# ZERO.net
KiCad netlist of a schematic drawn in Altium Designer
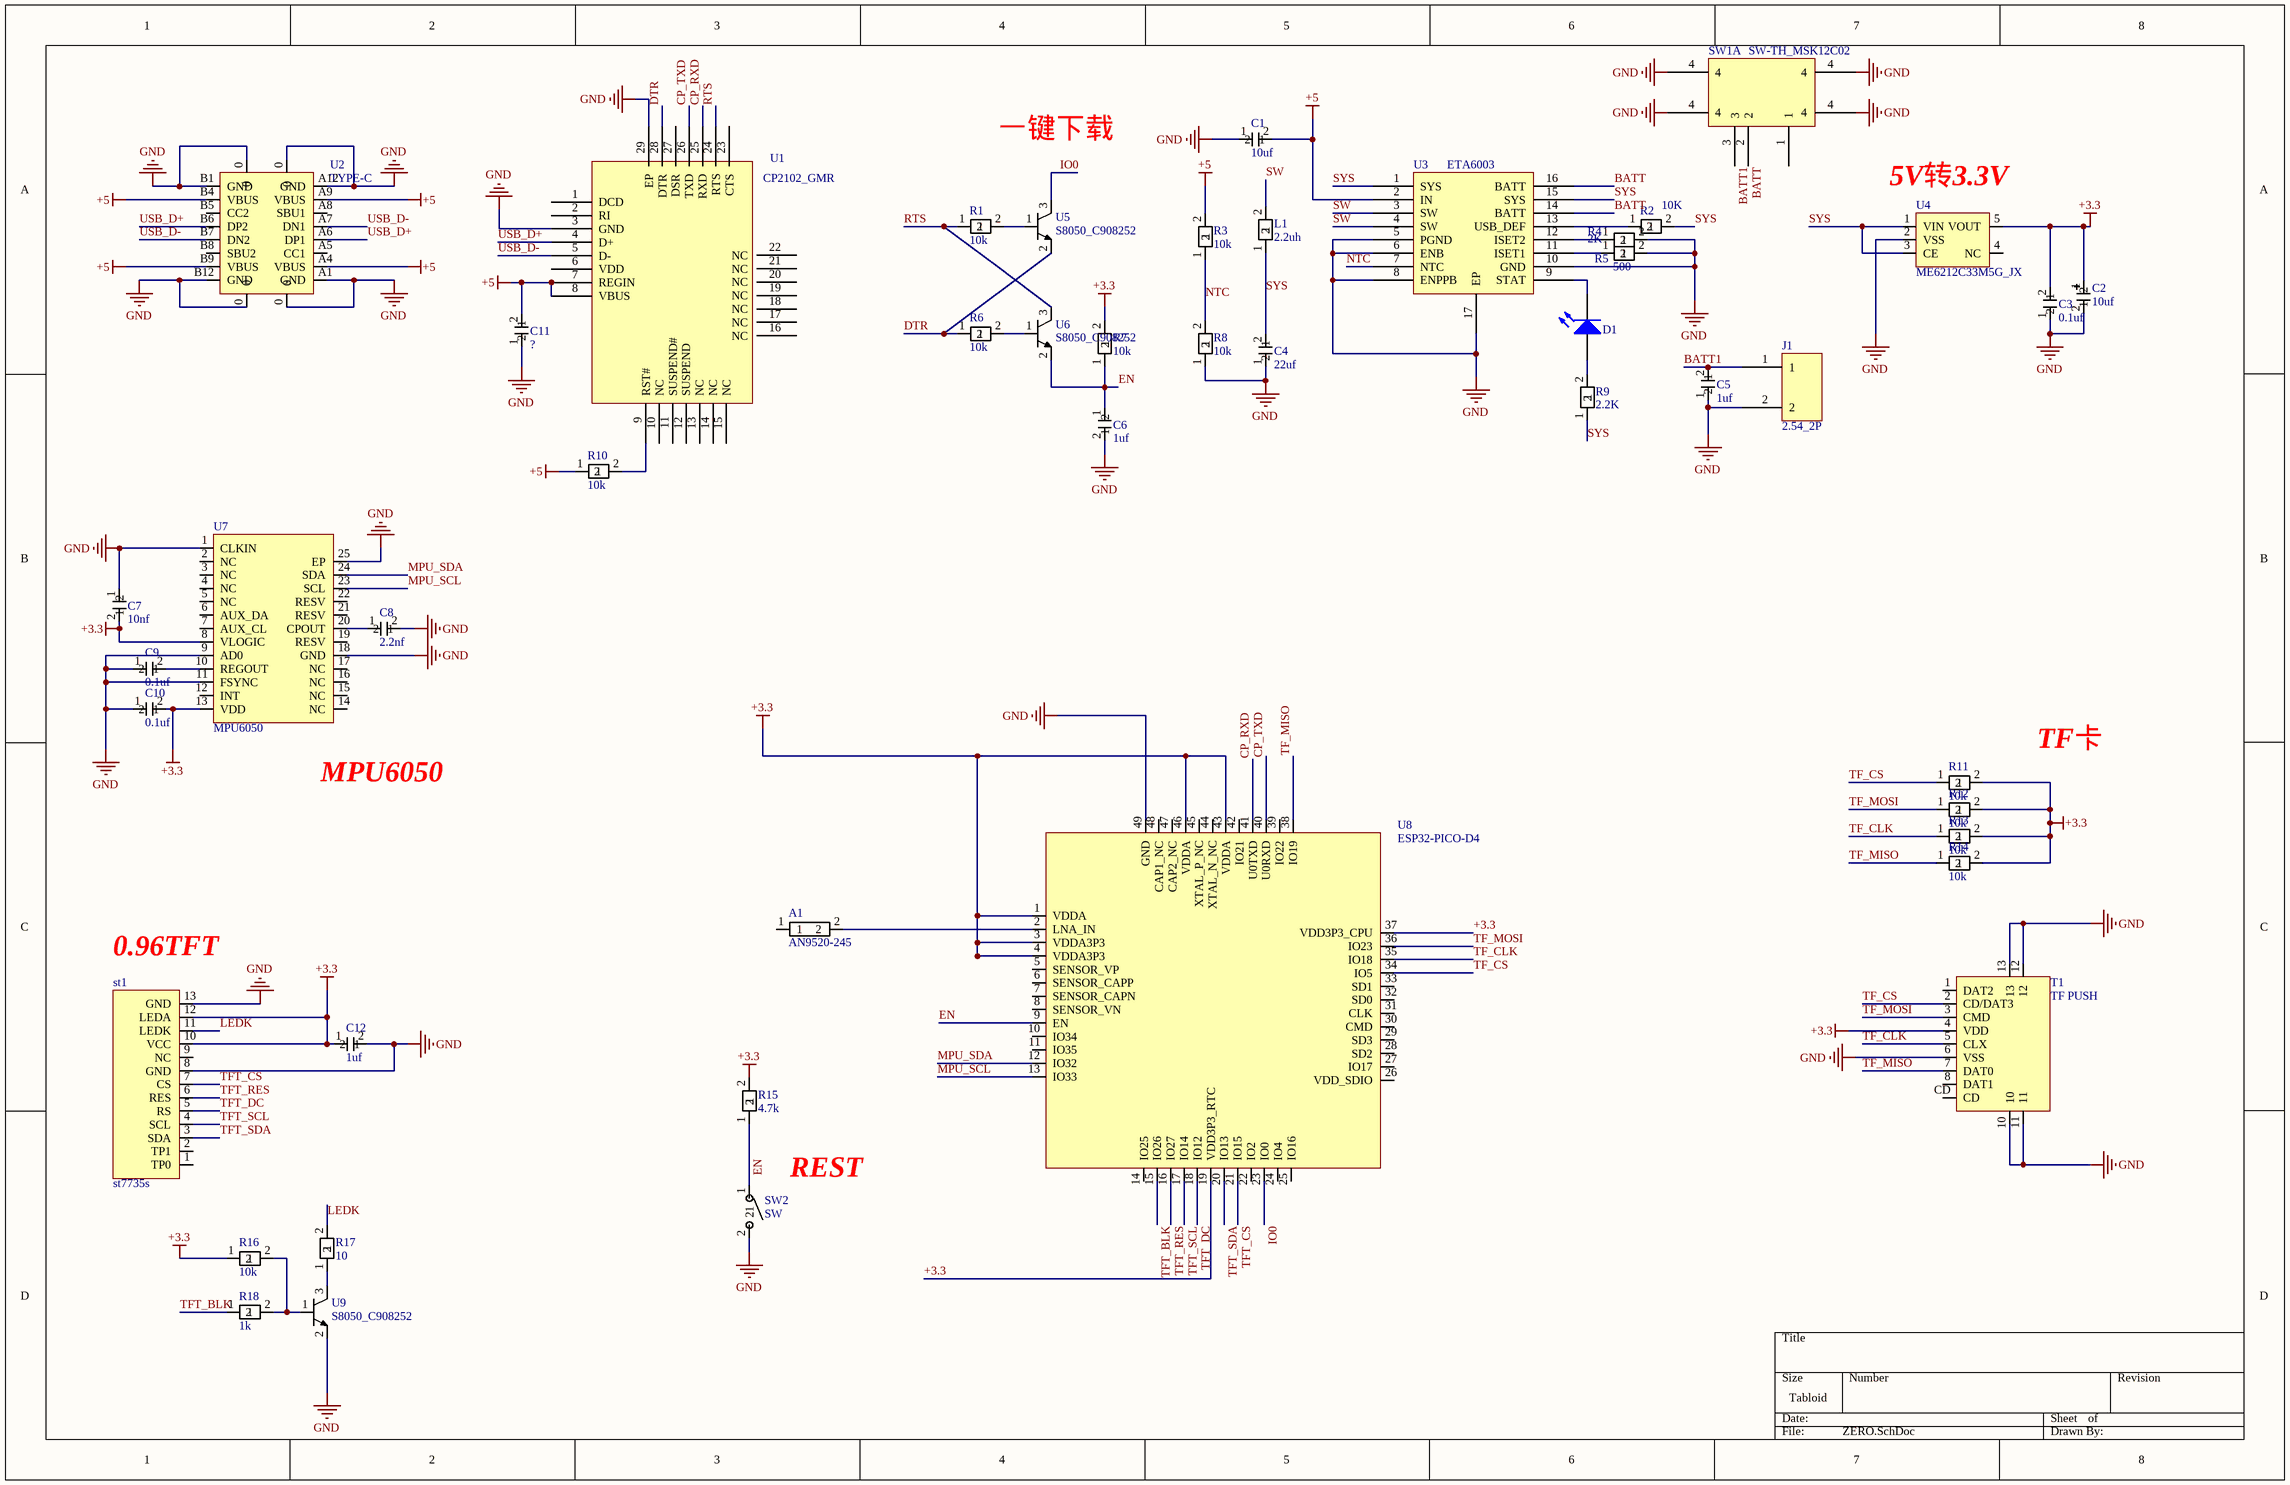
[diagram p0: ZERO.SchDoc]

(export (version "E")
  (design (tool "Eeschema 10.0.6"))
  (components
    (comp (ref "A1") (value "AN9520-245") (footprint "AN9520-245") (libsource (lib "My") (part "AN9520-245")))
    (comp (ref "C1") (value "10uf") (footprint "C0805") (libsource (lib "My") (part "C0805")))
    (comp (ref "C2") (value "10uf") (footprint "C+") (libsource (lib "My") (part "C+")))
    (comp (ref "C3") (value "0.1uf") (footprint "C0805") (libsource (lib "Schlib1") (part "C0805")))
    (comp (ref "C4") (value "22uf") (footprint "C0805") (libsource (lib "My") (part "C0805")))
    (comp (ref "C5") (value "1uf") (footprint "C0805") (libsource (lib "My") (part "C0805")))
    (comp (ref "C6") (value "1uf") (footprint "C0805") (libsource (lib "Schlib1") (part "C0805")))
    (comp (ref "C7") (value "10nf") (footprint "C0805") (libsource (lib "Schlib1") (part "C0805")))
    (comp (ref "C8") (value "2.2nf") (footprint "C0805") (libsource (lib "Schlib1") (part "C0805")))
    (comp (ref "C9") (value "0.1uf") (footprint "C0805") (libsource (lib "Schlib1") (part "C0805")))
    (comp (ref "C10") (value "0.1uf") (footprint "C0805") (libsource (lib "Schlib1") (part "C0805")))
    (comp (ref "C11") (value "?") (footprint "C0805") (libsource (lib "My") (part "C0805")))
    (comp (ref "C12") (value "1uf") (footprint "C0805") (libsource (lib "Schlib1") (part "C0805")))
    (comp (ref "D1")
      (value "LED 蓝 0805")
      (footprint "LED 蓝  0805")
      (libsource (lib "改好的库") (part "LED 蓝 0805"))
    )
    (comp (ref "J1") (value "2.54_2P") (footprint "2.54-2P") (libsource (lib "My") (part "2.54_2P")))
    (comp (ref "L1") (value "2.2uh") (footprint "R0805") (libsource (lib "My") (part "R0805")))
    (comp (ref "R1") (value "10k") (footprint "R0805") (libsource (lib "Schlib1") (part "R0805")))
    (comp (ref "R2") (value "10K") (footprint "R0805") (libsource (lib "My") (part "R0805")))
    (comp (ref "R3") (value "10k") (footprint "R0805") (libsource (lib "My") (part "R0805")))
    (comp (ref "R4") (value "2K") (footprint "R0805") (libsource (lib "My") (part "R0805")))
    (comp (ref "R5") (value "500") (footprint "R0805") (libsource (lib "My") (part "R0805")))
    (comp (ref "R6") (value "10k") (footprint "R0805") (libsource (lib "Schlib1") (part "R0805")))
    (comp (ref "R7") (value "10k") (footprint "R0805") (libsource (lib "Schlib1") (part "R0805")))
    (comp (ref "R8") (value "10k") (footprint "R0805") (libsource (lib "My") (part "R0805")))
    (comp (ref "R9") (value "2.2K") (footprint "R0805") (libsource (lib "My") (part "R0805")))
    (comp (ref "R10") (value "10k") (footprint "R0805") (libsource (lib "My") (part "R0805")))
    (comp (ref "R11") (value "10k") (footprint "R0805") (libsource (lib "Schlib1") (part "R0805")))
    (comp (ref "R12") (value "10k") (footprint "R0805") (libsource (lib "Schlib1") (part "R0805")))
    (comp (ref "R13") (value "10k") (footprint "R0805") (libsource (lib "Schlib1") (part "R0805")))
    (comp (ref "R14") (value "10k") (footprint "R0805") (libsource (lib "Schlib1") (part "R0805")))
    (comp (ref "R15") (value "4.7k") (footprint "R0805") (libsource (lib "Schlib1") (part "R0805")))
    (comp (ref "R16") (value "10k") (footprint "R0805") (libsource (lib "Schlib1") (part "R0805")))
    (comp (ref "R17") (value "10") (footprint "R0805") (libsource (lib "Schlib1") (part "R0805")))
    (comp (ref "R18") (value "1k") (footprint "R0805") (libsource (lib "Schlib1") (part "R0805")))
    (comp (ref "st1") (value "st7735s") (footprint "st7735s") (libsource (lib "Schlib1") (part "st7735s")))
    (comp (ref "SW1")
      (value "SW-TH_MSK12C02")
      (footprint "SW-TH_MSK12C02")
      (libsource (lib "My") (part "SW-TH_MSK12C02"))
    )
    (comp (ref "SW2") (value "SW") (footprint "SW") (libsource (lib "My") (part "SW")))
    (comp (ref "T1") (value "TF PUSH") (footprint "TF-SMD_TF-PUSH") (libsource (lib "My") (part "TF PUSH")))
    (comp (ref "U1") (value "CP2102_GMR") (footprint "CP2102_GMR") (libsource (lib "My") (part "CP2102_GMR")))
    (comp (ref "U2")
      (value "TYPE-C")
      (footprint "USB-C")
      (description "TYPE-C-31-M-12")
      (libsource (lib "My") (part "TYPE-C"))
    )
    (comp (ref "U3") (value "ETA6003") (footprint "ETA6003") (libsource (lib "My") (part "ETA6003")))
    (comp (ref "U4")
      (value "ME6212C33M5G_JX")
      (footprint "ME6212C33M5G_JX")
      (libsource (lib "My") (part "ME6212C33M5G_JX"))
    )
    (comp (ref "U5") (value "S8050_C908252") (footprint "s8050") (libsource (lib "My") (part "s8050")))
    (comp (ref "U6") (value "S8050_C908252") (footprint "s8050") (libsource (lib "My") (part "s8050")))
    (comp (ref "U7") (value "MPU6050") (footprint "MPU6050") (libsource (lib "My") (part "MPU6050")))
    (comp (ref "U8")
      (value "ESP32-PICO-D4")
      (footprint "ESP32-PICO-D4")
      (libsource (lib "My") (part "ESP32-PICO-D4"))
    )
    (comp (ref "U9") (value "S8050_C908252") (footprint "s8050") (libsource (lib "My") (part "s8050")))
  )
  (nets
    (net (code "1") (name "+3.3") (class "Default")
      (node (ref "C10") (pin "2") (pinfunction "2_2") (pintype "passive"))
      (node (ref "C12") (pin "1") (pinfunction "1_1") (pintype "passive"))
      (node (ref "C2") (pin "1") (pinfunction "1_1") (pintype "passive"))
      (node (ref "C3") (pin "2") (pinfunction "2_2") (pintype "passive"))
      (node (ref "C7") (pin "2") (pinfunction "2_2") (pintype "passive"))
      (node (ref "R11") (pin "2") (pinfunction "2_2") (pintype "passive"))
      (node (ref "R12") (pin "2") (pinfunction "2_2") (pintype "passive"))
      (node (ref "R13") (pin "2") (pinfunction "2_2") (pintype "passive"))
      (node (ref "R14") (pin "2") (pinfunction "2_2") (pintype "passive"))
      (node (ref "R15") (pin "2") (pinfunction "2_2") (pintype "passive"))
      (node (ref "R16") (pin "1") (pinfunction "1_1") (pintype "passive"))
      (node (ref "R7") (pin "2") (pinfunction "2_2") (pintype "passive"))
      (node (ref "T1") (pin "4") (pinfunction "VDD_4") (pintype "passive"))
      (node (ref "U4") (pin "5") (pinfunction "VOUT_5") (pintype "passive"))
      (node (ref "U7") (pin "13") (pinfunction "VDD_13") (pintype "passive"))
      (node (ref "U7") (pin "8") (pinfunction "VLOGIC_8") (pintype "passive"))
      (node (ref "U8") (pin "1") (pinfunction "VDDA_1") (pintype "passive"))
      (node (ref "U8") (pin "19") (pinfunction "VDD3P3_RTC_19") (pintype "passive"))
      (node (ref "U8") (pin "3") (pinfunction "VDDA3P3_3") (pintype "passive"))
      (node (ref "U8") (pin "37") (pinfunction "VDD3P3_CPU_37") (pintype "passive"))
      (node (ref "U8") (pin "4") (pinfunction "VDDA3P3_4") (pintype "passive"))
      (node (ref "U8") (pin "43") (pinfunction "VDDA_43") (pintype "passive"))
      (node (ref "U8") (pin "46") (pinfunction "VDDA_46") (pintype "passive"))
      (node (ref "st1") (pin "10") (pinfunction "VCC_10") (pintype "passive"))
      (node (ref "st1") (pin "12") (pinfunction "LEDA_12") (pintype "passive"))
    )
    (net (code "2") (name "+5") (class "Default")
      (node (ref "C1") (pin "2") (pinfunction "2_2") (pintype "passive"))
      (node (ref "C11") (pin "2") (pinfunction "2_2") (pintype "passive"))
      (node (ref "R10") (pin "1") (pinfunction "1_1") (pintype "passive"))
      (node (ref "R3") (pin "2") (pinfunction "2_2") (pintype "passive"))
      (node (ref "U1") (pin "7") (pinfunction "REGIN_7") (pintype "passive"))
      (node (ref "U1") (pin "8") (pinfunction "VBUS_8") (pintype "passive"))
      (node (ref "U2") (pin "A4") (pinfunction "VBUS_A4") (pintype "passive"))
      (node (ref "U2") (pin "A9") (pinfunction "VBUS_A9") (pintype "passive"))
      (node (ref "U2") (pin "B4") (pinfunction "VBUS_B4") (pintype "passive"))
      (node (ref "U2") (pin "B9") (pinfunction "VBUS_B9") (pintype "passive"))
      (node (ref "U3") (pin "2") (pinfunction "IN_2") (pintype "passive"))
    )
    (net (code "4") (name "/BATT") (class "Default")
      (node (ref "SW1") (pin "2") (pinfunction "2_2") (pintype "passive"))
      (node (ref "U3") (pin "14") (pinfunction "BATT_14") (pintype "passive"))
      (node (ref "U3") (pin "16") (pinfunction "BATT_16") (pintype "passive"))
    )
    (net (code "5") (name "/BATT1") (class "Default")
      (node (ref "C5") (pin "2") (pinfunction "2_2") (pintype "passive"))
      (node (ref "J1") (pin "1") (pinfunction "1_1") (pintype "passive"))
      (node (ref "SW1") (pin "3") (pinfunction "3_3") (pintype "passive"))
    )
    (net (code "6") (name "/CP_RXD") (class "Default")
      (node (ref "U1") (pin "25") (pinfunction "RXD_25") (pintype "passive"))
      (node (ref "U8") (pin "41") (pinfunction "U0TXD_41") (pintype "passive"))
    )
    (net (code "7") (name "/CP_TXD") (class "Default")
      (node (ref "U1") (pin "26") (pinfunction "TXD_26") (pintype "passive"))
      (node (ref "U8") (pin "40") (pinfunction "U0RXD_40") (pintype "passive"))
    )
    (net (code "8") (name "/DTR") (class "Default")
      (node (ref "R6") (pin "1") (pinfunction "1_1") (pintype "passive"))
      (node (ref "U1") (pin "28") (pinfunction "DTR_28") (pintype "passive"))
      (node (ref "U5") (pin "2") (pinfunction "E_2") (pintype "passive"))
    )
    (net (code "9") (name "/EN") (class "Default")
      (node (ref "C6") (pin "1") (pinfunction "1_1") (pintype "passive"))
      (node (ref "R15") (pin "1") (pinfunction "1_1") (pintype "passive"))
      (node (ref "R7") (pin "1") (pinfunction "1_1") (pintype "passive"))
      (node (ref "SW2") (pin "1") (pinfunction "1_1") (pintype "passive"))
      (node (ref "U6") (pin "2") (pinfunction "E_2") (pintype "passive"))
      (node (ref "U8") (pin "9") (pinfunction "EN_9") (pintype "passive"))
    )
    (net (code "10") (name "/IO0") (class "Default")
      (node (ref "U5") (pin "3") (pinfunction "C_3") (pintype "passive"))
      (node (ref "U8") (pin "23") (pinfunction "IO0_23") (pintype "passive"))
    )
    (net (code "11") (name "/LEDK") (class "Default")
      (node (ref "R17") (pin "2") (pinfunction "2_2") (pintype "passive"))
      (node (ref "st1") (pin "11") (pinfunction "LEDK_11") (pintype "passive"))
    )
    (net (code "12") (name "/MPU_SCL") (class "Default")
      (node (ref "U7") (pin "23") (pinfunction "SCL_23") (pintype "passive"))
      (node (ref "U8") (pin "13") (pinfunction "IO33_13") (pintype "passive"))
    )
    (net (code "13") (name "/MPU_SDA") (class "Default")
      (node (ref "U7") (pin "24") (pinfunction "SDA_24") (pintype "passive"))
      (node (ref "U8") (pin "12") (pinfunction "IO32_12") (pintype "passive"))
    )
    (net (code "14") (name "/NTC") (class "Default")
      (node (ref "R3") (pin "1") (pinfunction "1_1") (pintype "passive"))
      (node (ref "R8") (pin "2") (pinfunction "2_2") (pintype "passive"))
      (node (ref "U3") (pin "7") (pinfunction "NTC_7") (pintype "passive"))
    )
    (net (code "15") (name "/RTS") (class "Default")
      (node (ref "R1") (pin "1") (pinfunction "1_1") (pintype "passive"))
      (node (ref "U1") (pin "24") (pinfunction "RTS_24") (pintype "passive"))
      (node (ref "U6") (pin "3") (pinfunction "C_3") (pintype "passive"))
    )
    (net (code "16") (name "/SW") (class "Default")
      (node (ref "L1") (pin "2") (pinfunction "2_2") (pintype "passive"))
      (node (ref "U3") (pin "3") (pinfunction "SW_3") (pintype "passive"))
      (node (ref "U3") (pin "4") (pinfunction "SW_4") (pintype "passive"))
    )
    (net (code "17") (name "/SYS") (class "Default")
      (node (ref "C4") (pin "2") (pinfunction "2_2") (pintype "passive"))
      (node (ref "L1") (pin "1") (pinfunction "1_1") (pintype "passive"))
      (node (ref "R2") (pin "2") (pinfunction "2_2") (pintype "passive"))
      (node (ref "R9") (pin "1") (pinfunction "1_1") (pintype "passive"))
      (node (ref "U3") (pin "1") (pinfunction "SYS_1") (pintype "passive"))
      (node (ref "U3") (pin "15") (pinfunction "SYS_15") (pintype "passive"))
      (node (ref "U4") (pin "1") (pinfunction "VIN_1") (pintype "passive"))
      (node (ref "U4") (pin "3") (pinfunction "CE_3") (pintype "passive"))
    )
    (net (code "18") (name "/TFT_BLK") (class "Default")
      (node (ref "R18") (pin "1") (pinfunction "1_1") (pintype "passive"))
      (node (ref "U8") (pin "15") (pinfunction "IO26_15") (pintype "passive"))
    )
    (net (code "19") (name "/TFT_CS") (class "Default")
      (node (ref "U8") (pin "21") (pinfunction "IO15_21") (pintype "passive"))
      (node (ref "st1") (pin "7") (pinfunction "CS_7") (pintype "passive"))
    )
    (net (code "20") (name "/TFT_DC") (class "Default")
      (node (ref "U8") (pin "18") (pinfunction "IO12_18") (pintype "passive"))
      (node (ref "st1") (pin "5") (pinfunction "RS_5") (pintype "passive"))
    )
    (net (code "21") (name "/TFT_RES") (class "Default")
      (node (ref "U8") (pin "16") (pinfunction "IO27_16") (pintype "passive"))
      (node (ref "st1") (pin "6") (pinfunction "RES_6") (pintype "passive"))
    )
    (net (code "22") (name "/TFT_SCL") (class "Default")
      (node (ref "U8") (pin "17") (pinfunction "IO14_17") (pintype "passive"))
      (node (ref "st1") (pin "4") (pinfunction "SCL_4") (pintype "passive"))
    )
    (net (code "23") (name "/TFT_SDA") (class "Default")
      (node (ref "U8") (pin "20") (pinfunction "IO13_20") (pintype "passive"))
      (node (ref "st1") (pin "3") (pinfunction "SDA_3") (pintype "passive"))
    )
    (net (code "24") (name "/TF_CLK") (class "Default")
      (node (ref "R13") (pin "1") (pinfunction "1_1") (pintype "passive"))
      (node (ref "T1") (pin "5") (pinfunction "CLX_5") (pintype "passive"))
      (node (ref "U8") (pin "35") (pinfunction "IO18_35") (pintype "passive"))
    )
    (net (code "25") (name "/TF_CS") (class "Default")
      (node (ref "R11") (pin "1") (pinfunction "1_1") (pintype "passive"))
      (node (ref "T1") (pin "2") (pinfunction "CD/DAT3_2") (pintype "passive"))
      (node (ref "U8") (pin "34") (pinfunction "IO5_34") (pintype "passive"))
    )
    (net (code "26") (name "/TF_MISO") (class "Default")
      (node (ref "R14") (pin "1") (pinfunction "1_1") (pintype "passive"))
      (node (ref "T1") (pin "7") (pinfunction "DAT0_7") (pintype "passive"))
      (node (ref "U8") (pin "38") (pinfunction "IO19_38") (pintype "passive"))
    )
    (net (code "27") (name "/TF_MOSI") (class "Default")
      (node (ref "R12") (pin "1") (pinfunction "1_1") (pintype "passive"))
      (node (ref "T1") (pin "3") (pinfunction "CMD_3") (pintype "passive"))
      (node (ref "U8") (pin "36") (pinfunction "IO23_36") (pintype "passive"))
    )
    (net (code "28") (name "/USB_D+") (class "Default")
      (node (ref "U1") (pin "4") (pinfunction "D+_4") (pintype "passive"))
      (node (ref "U2") (pin "A6") (pinfunction "DP1_A6") (pintype "passive"))
      (node (ref "U2") (pin "B6") (pinfunction "DP2_B6") (pintype "passive"))
    )
    (net (code "29") (name "/USB_D-") (class "Default")
      (node (ref "U1") (pin "5") (pinfunction "D-_5") (pintype "passive"))
      (node (ref "U2") (pin "A7") (pinfunction "DN1_A7") (pintype "passive"))
      (node (ref "U2") (pin "B7") (pinfunction "DN2_B7") (pintype "passive"))
    )
    (net (code "30") (name "GND") (class "Default")
      (node (ref "C1") (pin "1") (pinfunction "1_1") (pintype "passive"))
      (node (ref "C10") (pin "1") (pinfunction "1_1") (pintype "passive"))
      (node (ref "C11") (pin "1") (pinfunction "1_1") (pintype "passive"))
      (node (ref "C12") (pin "2") (pinfunction "2_2") (pintype "passive"))
      (node (ref "C2") (pin "2") (pinfunction "2_2") (pintype "passive"))
      (node (ref "C3") (pin "1") (pinfunction "1_1") (pintype "passive"))
      (node (ref "C4") (pin "1") (pinfunction "1_1") (pintype "passive"))
      (node (ref "C5") (pin "1") (pinfunction "1_1") (pintype "passive"))
      (node (ref "C6") (pin "2") (pinfunction "2_2") (pintype "passive"))
      (node (ref "C7") (pin "1") (pinfunction "1_1") (pintype "passive"))
      (node (ref "C8") (pin "2") (pinfunction "2_2") (pintype "passive"))
      (node (ref "C9") (pin "1") (pinfunction "1_1") (pintype "passive"))
      (node (ref "J1") (pin "2") (pinfunction "2_2") (pintype "passive"))
      (node (ref "R4") (pin "2") (pinfunction "2_2") (pintype "passive"))
      (node (ref "R5") (pin "2") (pinfunction "2_2") (pintype "passive"))
      (node (ref "R8") (pin "1") (pinfunction "1_1") (pintype "passive"))
      (node (ref "SW1") (pin "4") (pinfunction "4_4") (pintype "passive"))
      (node (ref "SW2") (pin "2") (pinfunction "2_2") (pintype "passive"))
      (node (ref "T1") (pin "10") (pinfunction "10_10") (pintype "passive"))
      (node (ref "T1") (pin "11") (pinfunction "11_11") (pintype "passive"))
      (node (ref "T1") (pin "12") (pinfunction "12_12") (pintype "passive"))
      (node (ref "T1") (pin "13") (pinfunction "13_13") (pintype "passive"))
      (node (ref "T1") (pin "6") (pinfunction "VSS_6") (pintype "passive"))
      (node (ref "U1") (pin "29") (pinfunction "EP_29") (pintype "passive"))
      (node (ref "U1") (pin "3") (pinfunction "GND_3") (pintype "passive"))
      (node (ref "U2") (pin "0") (pinfunction "0_0") (pintype "passive"))
      (node (ref "U2") (pin "A1") (pinfunction "GND_A1") (pintype "passive"))
      (node (ref "U2") (pin "A12") (pinfunction "GND_A12") (pintype "passive"))
      (node (ref "U2") (pin "B1") (pinfunction "GND_B1") (pintype "passive"))
      (node (ref "U2") (pin "B12") (pinfunction "GND_B12") (pintype "passive"))
      (node (ref "U3") (pin "10") (pinfunction "GND_10") (pintype "passive"))
      (node (ref "U3") (pin "17") (pinfunction "EP_17") (pintype "passive"))
      (node (ref "U3") (pin "5") (pinfunction "PGND_5") (pintype "passive"))
      (node (ref "U3") (pin "6") (pinfunction "ENB_6") (pintype "passive"))
      (node (ref "U3") (pin "8") (pinfunction "ENPPB_8") (pintype "passive"))
      (node (ref "U4") (pin "2") (pinfunction "VSS_2") (pintype "passive"))
      (node (ref "U7") (pin "1") (pinfunction "CLKIN_1") (pintype "passive"))
      (node (ref "U7") (pin "11") (pinfunction "FSYNC_11") (pintype "passive"))
      (node (ref "U7") (pin "18") (pinfunction "GND_18") (pintype "passive"))
      (node (ref "U7") (pin "25") (pinfunction "EP_25") (pintype "passive"))
      (node (ref "U7") (pin "9") (pinfunction "AD0_9") (pintype "passive"))
      (node (ref "U8") (pin "49") (pinfunction "GND_49") (pintype "passive"))
      (node (ref "U9") (pin "2") (pinfunction "E_2") (pintype "passive"))
      (node (ref "st1") (pin "13") (pinfunction "GND_13") (pintype "passive"))
      (node (ref "st1") (pin "8") (pinfunction "GND_8") (pintype "passive"))
    )
    (net (code "31") (name "Net-(D1-A)") (class "Default")
      (node (ref "D1") (pin "1") (pinfunction "A_1") (pintype "passive"))
      (node (ref "R9") (pin "2") (pinfunction "2_2") (pintype "passive"))
    )
    (net (code "32") (name "Net-(D1-K)") (class "Default")
      (node (ref "D1") (pin "2") (pinfunction "K_2") (pintype "passive"))
      (node (ref "U3") (pin "9") (pinfunction "STAT_9") (pintype "passive"))
    )
    (net (code "33") (name "Net-(U1-RST#)") (class "Default")
      (node (ref "R10") (pin "2") (pinfunction "2_2") (pintype "passive"))
      (node (ref "U1") (pin "9") (pinfunction "RST#_9") (pintype "passive"))
    )
    (net (code "34") (name "Net-(U3-ISET1)") (class "Default")
      (node (ref "R5") (pin "1") (pinfunction "1_1") (pintype "passive"))
      (node (ref "U3") (pin "11") (pinfunction "ISET1_11") (pintype "passive"))
    )
    (net (code "35") (name "Net-(U3-ISET2)") (class "Default")
      (node (ref "R4") (pin "1") (pinfunction "1_1") (pintype "passive"))
      (node (ref "U3") (pin "12") (pinfunction "ISET2_12") (pintype "passive"))
    )
    (net (code "36") (name "Net-(U3-USB_DEF)") (class "Default")
      (node (ref "R2") (pin "1") (pinfunction "1_1") (pintype "passive"))
      (node (ref "U3") (pin "13") (pinfunction "USB_DEF_13") (pintype "passive"))
    )
    (net (code "37") (name "Net-(U5-B)") (class "Default")
      (node (ref "R1") (pin "2") (pinfunction "2_2") (pintype "passive"))
      (node (ref "U5") (pin "1") (pinfunction "B_1") (pintype "passive"))
    )
    (net (code "38") (name "Net-(U6-B)") (class "Default")
      (node (ref "R6") (pin "2") (pinfunction "2_2") (pintype "passive"))
      (node (ref "U6") (pin "1") (pinfunction "B_1") (pintype "passive"))
    )
    (net (code "39") (name "Net-(U7-CPOUT)") (class "Default")
      (node (ref "C8") (pin "1") (pinfunction "1_1") (pintype "passive"))
      (node (ref "U7") (pin "20") (pinfunction "CPOUT_20") (pintype "passive"))
    )
    (net (code "40") (name "Net-(U7-REGOUT)") (class "Default")
      (node (ref "C9") (pin "2") (pinfunction "2_2") (pintype "passive"))
      (node (ref "U7") (pin "10") (pinfunction "REGOUT_10") (pintype "passive"))
    )
    (net (code "41") (name "Net-(U8-LNA_IN)") (class "Default")
      (node (ref "A1") (pin "2") (pinfunction "2_2") (pintype "passive"))
      (node (ref "U8") (pin "2") (pinfunction "LNA_IN_2") (pintype "passive"))
    )
    (net (code "42") (name "Net-(U9-B)") (class "Default")
      (node (ref "R16") (pin "2") (pinfunction "2_2") (pintype "passive"))
      (node (ref "R18") (pin "2") (pinfunction "2_2") (pintype "passive"))
      (node (ref "U9") (pin "1") (pinfunction "B_1") (pintype "passive"))
    )
    (net (code "43") (name "Net-(U9-C)") (class "Default")
      (node (ref "R17") (pin "1") (pinfunction "1_1") (pintype "passive"))
      (node (ref "U9") (pin "3") (pinfunction "C_3") (pintype "passive"))
    )
    (net (code "44") (name "unconnected-(A1-Pad1)") (class "Default")
      (node (ref "A1") (pin "1") (pinfunction "1_1") (pintype "passive"))
    )
    (net (code "45") (name "unconnected-(SW1-Pad1)") (class "Default")
      (node (ref "SW1") (pin "1") (pinfunction "1_1") (pintype "passive"))
    )
    (net (code "46") (name "unconnected-(T1-DAT1-Pad8)") (class "Default")
      (node (ref "T1") (pin "8") (pinfunction "DAT1_8") (pintype "passive"))
    )
    (net (code "47") (name "unconnected-(T1-DAT2-Pad1)") (class "Default")
      (node (ref "T1") (pin "1") (pinfunction "DAT2_1") (pintype "passive"))
    )
    (net (code "48") (name "unconnected-(T1-PadCD)") (class "Default")
      (node (ref "T1") (pin "CD") (pinfunction "CD_CD") (pintype "passive"))
    )
    (net (code "49") (name "unconnected-(U1-CTS-Pad23)") (class "Default")
      (node (ref "U1") (pin "23") (pinfunction "CTS_23") (pintype "passive"))
    )
    (net (code "50") (name "unconnected-(U1-DCD-Pad1)") (class "Default")
      (node (ref "U1") (pin "1") (pinfunction "DCD_1") (pintype "passive"))
    )
    (net (code "51") (name "unconnected-(U1-DSR-Pad27)") (class "Default")
      (node (ref "U1") (pin "27") (pinfunction "DSR_27") (pintype "passive"))
    )
    (net (code "52") (name "unconnected-(U1-NC-Pad10)") (class "Default")
      (node (ref "U1") (pin "10") (pinfunction "NC_10") (pintype "passive"))
    )
    (net (code "53") (name "unconnected-(U1-NC-Pad13)") (class "Default")
      (node (ref "U1") (pin "13") (pinfunction "NC_13") (pintype "passive"))
    )
    (net (code "54") (name "unconnected-(U1-NC-Pad14)") (class "Default")
      (node (ref "U1") (pin "14") (pinfunction "NC_14") (pintype "passive"))
    )
    (net (code "55") (name "unconnected-(U1-NC-Pad15)") (class "Default")
      (node (ref "U1") (pin "15") (pinfunction "NC_15") (pintype "passive"))
    )
    (net (code "56") (name "unconnected-(U1-NC-Pad16)") (class "Default")
      (node (ref "U1") (pin "16") (pinfunction "NC_16") (pintype "passive"))
    )
    (net (code "57") (name "unconnected-(U1-NC-Pad17)") (class "Default")
      (node (ref "U1") (pin "17") (pinfunction "NC_17") (pintype "passive"))
    )
    (net (code "58") (name "unconnected-(U1-NC-Pad18)") (class "Default")
      (node (ref "U1") (pin "18") (pinfunction "NC_18") (pintype "passive"))
    )
    (net (code "59") (name "unconnected-(U1-NC-Pad19)") (class "Default")
      (node (ref "U1") (pin "19") (pinfunction "NC_19") (pintype "passive"))
    )
    (net (code "60") (name "unconnected-(U1-NC-Pad20)") (class "Default")
      (node (ref "U1") (pin "20") (pinfunction "NC_20") (pintype "passive"))
    )
    (net (code "61") (name "unconnected-(U1-NC-Pad21)") (class "Default")
      (node (ref "U1") (pin "21") (pinfunction "NC_21") (pintype "passive"))
    )
    (net (code "62") (name "unconnected-(U1-NC-Pad22)") (class "Default")
      (node (ref "U1") (pin "22") (pinfunction "NC_22") (pintype "passive"))
    )
    (net (code "63") (name "unconnected-(U1-RI-Pad2)") (class "Default")
      (node (ref "U1") (pin "2") (pinfunction "RI_2") (pintype "passive"))
    )
    (net (code "64") (name "unconnected-(U1-SUSPEND#-Pad11)") (class "Default")
      (node (ref "U1") (pin "11") (pinfunction "SUSPEND#_11") (pintype "passive"))
    )
    (net (code "65") (name "unconnected-(U1-SUSPEND-Pad12)") (class "Default")
      (node (ref "U1") (pin "12") (pinfunction "SUSPEND_12") (pintype "passive"))
    )
    (net (code "66") (name "unconnected-(U1-VDD-Pad6)") (class "Default")
      (node (ref "U1") (pin "6") (pinfunction "VDD_6") (pintype "passive"))
    )
    (net (code "67") (name "unconnected-(U2-CC1-PadA5)") (class "Default")
      (node (ref "U2") (pin "A5") (pinfunction "CC1_A5") (pintype "passive"))
    )
    (net (code "68") (name "unconnected-(U2-CC2-PadB5)") (class "Default")
      (node (ref "U2") (pin "B5") (pinfunction "CC2_B5") (pintype "passive"))
    )
    (net (code "69") (name "unconnected-(U2-SBU1-PadA8)") (class "Default")
      (node (ref "U2") (pin "A8") (pinfunction "SBU1_A8") (pintype "passive"))
    )
    (net (code "70") (name "unconnected-(U2-SBU2-PadB8)") (class "Default")
      (node (ref "U2") (pin "B8") (pinfunction "SBU2_B8") (pintype "passive"))
    )
    (net (code "71") (name "unconnected-(U4-NC-Pad4)") (class "Default")
      (node (ref "U4") (pin "4") (pinfunction "NC_4") (pintype "passive"))
    )
    (net (code "72") (name "unconnected-(U7-AUX_CL-Pad7)") (class "Default")
      (node (ref "U7") (pin "7") (pinfunction "AUX_CL_7") (pintype "passive"))
    )
    (net (code "73") (name "unconnected-(U7-AUX_DA-Pad6)") (class "Default")
      (node (ref "U7") (pin "6") (pinfunction "AUX_DA_6") (pintype "passive"))
    )
    (net (code "74") (name "unconnected-(U7-INT-Pad12)") (class "Default")
      (node (ref "U7") (pin "12") (pinfunction "INT_12") (pintype "passive"))
    )
    (net (code "75") (name "unconnected-(U7-NC-Pad2)") (class "Default")
      (node (ref "U7") (pin "2") (pinfunction "NC_2") (pintype "passive"))
    )
    (net (code "76") (name "unconnected-(U7-NC-Pad3)") (class "Default")
      (node (ref "U7") (pin "3") (pinfunction "NC_3") (pintype "passive"))
    )
    (net (code "77") (name "unconnected-(U7-NC-Pad4)") (class "Default")
      (node (ref "U7") (pin "4") (pinfunction "NC_4") (pintype "passive"))
    )
    (net (code "78") (name "unconnected-(U7-NC-Pad5)") (class "Default")
      (node (ref "U7") (pin "5") (pinfunction "NC_5") (pintype "passive"))
    )
    (net (code "79") (name "unconnected-(U7-NC-Pad14)") (class "Default")
      (node (ref "U7") (pin "14") (pinfunction "NC_14") (pintype "passive"))
    )
    (net (code "80") (name "unconnected-(U7-NC-Pad15)") (class "Default")
      (node (ref "U7") (pin "15") (pinfunction "NC_15") (pintype "passive"))
    )
    (net (code "81") (name "unconnected-(U7-NC-Pad16)") (class "Default")
      (node (ref "U7") (pin "16") (pinfunction "NC_16") (pintype "passive"))
    )
    (net (code "82") (name "unconnected-(U7-NC-Pad17)") (class "Default")
      (node (ref "U7") (pin "17") (pinfunction "NC_17") (pintype "passive"))
    )
    (net (code "83") (name "unconnected-(U7-RESV-Pad19)") (class "Default")
      (node (ref "U7") (pin "19") (pinfunction "RESV_19") (pintype "passive"))
    )
    (net (code "84") (name "unconnected-(U7-RESV-Pad21)") (class "Default")
      (node (ref "U7") (pin "21") (pinfunction "RESV_21") (pintype "passive"))
    )
    (net (code "85") (name "unconnected-(U7-RESV-Pad22)") (class "Default")
      (node (ref "U7") (pin "22") (pinfunction "RESV_22") (pintype "passive"))
    )
    (net (code "86") (name "unconnected-(U8-CAP1_NC-Pad48)") (class "Default")
      (node (ref "U8") (pin "48") (pinfunction "CAP1_NC_48") (pintype "passive"))
    )
    (net (code "87") (name "unconnected-(U8-CAP2_NC-Pad47)") (class "Default")
      (node (ref "U8") (pin "47") (pinfunction "CAP2_NC_47") (pintype "passive"))
    )
    (net (code "88") (name "unconnected-(U8-CLK-Pad31)") (class "Default")
      (node (ref "U8") (pin "31") (pinfunction "CLK_31") (pintype "passive"))
    )
    (net (code "89") (name "unconnected-(U8-CMD-Pad30)") (class "Default")
      (node (ref "U8") (pin "30") (pinfunction "CMD_30") (pintype "passive"))
    )
    (net (code "90") (name "unconnected-(U8-IO2-Pad22)") (class "Default")
      (node (ref "U8") (pin "22") (pinfunction "IO2_22") (pintype "passive"))
    )
    (net (code "91") (name "unconnected-(U8-IO4-Pad24)") (class "Default")
      (node (ref "U8") (pin "24") (pinfunction "IO4_24") (pintype "passive"))
    )
    (net (code "92") (name "unconnected-(U8-IO16-Pad25)") (class "Default")
      (node (ref "U8") (pin "25") (pinfunction "IO16_25") (pintype "passive"))
    )
    (net (code "93") (name "unconnected-(U8-IO17-Pad27)") (class "Default")
      (node (ref "U8") (pin "27") (pinfunction "IO17_27") (pintype "passive"))
    )
    (net (code "94") (name "unconnected-(U8-IO21-Pad42)") (class "Default")
      (node (ref "U8") (pin "42") (pinfunction "IO21_42") (pintype "passive"))
    )
    (net (code "95") (name "unconnected-(U8-IO22-Pad39)") (class "Default")
      (node (ref "U8") (pin "39") (pinfunction "IO22_39") (pintype "passive"))
    )
    (net (code "96") (name "unconnected-(U8-IO25-Pad14)") (class "Default")
      (node (ref "U8") (pin "14") (pinfunction "IO25_14") (pintype "passive"))
    )
    (net (code "97") (name "unconnected-(U8-IO34-Pad10)") (class "Default")
      (node (ref "U8") (pin "10") (pinfunction "IO34_10") (pintype "passive"))
    )
    (net (code "98") (name "unconnected-(U8-IO35-Pad11)") (class "Default")
      (node (ref "U8") (pin "11") (pinfunction "IO35_11") (pintype "passive"))
    )
    (net (code "99") (name "unconnected-(U8-SD0-Pad32)") (class "Default")
      (node (ref "U8") (pin "32") (pinfunction "SD0_32") (pintype "passive"))
    )
    (net (code "100") (name "unconnected-(U8-SD1-Pad33)") (class "Default")
      (node (ref "U8") (pin "33") (pinfunction "SD1_33") (pintype "passive"))
    )
    (net (code "101") (name "unconnected-(U8-SD2-Pad28)") (class "Default")
      (node (ref "U8") (pin "28") (pinfunction "SD2_28") (pintype "passive"))
    )
    (net (code "102") (name "unconnected-(U8-SD3-Pad29)") (class "Default")
      (node (ref "U8") (pin "29") (pinfunction "SD3_29") (pintype "passive"))
    )
    (net (code "103") (name "unconnected-(U8-SENSOR_CAPN-Pad7)") (class "Default")
      (node (ref "U8") (pin "7") (pinfunction "SENSOR_CAPN_7") (pintype "passive"))
    )
    (net (code "104") (name "unconnected-(U8-SENSOR_CAPP-Pad6)") (class "Default")
      (node (ref "U8") (pin "6") (pinfunction "SENSOR_CAPP_6") (pintype "passive"))
    )
    (net (code "105") (name "unconnected-(U8-SENSOR_VN-Pad8)") (class "Default")
      (node (ref "U8") (pin "8") (pinfunction "SENSOR_VN_8") (pintype "passive"))
    )
    (net (code "106") (name "unconnected-(U8-SENSOR_VP-Pad5)") (class "Default")
      (node (ref "U8") (pin "5") (pinfunction "SENSOR_VP_5") (pintype "passive"))
    )
    (net (code "107") (name "unconnected-(U8-VDD_SDIO-Pad26)") (class "Default")
      (node (ref "U8") (pin "26") (pinfunction "VDD_SDIO_26") (pintype "passive"))
    )
    (net (code "108") (name "unconnected-(U8-XTAL_N_NC-Pad44)") (class "Default")
      (node (ref "U8") (pin "44") (pinfunction "XTAL_N_NC_44") (pintype "passive"))
    )
    (net (code "109") (name "unconnected-(U8-XTAL_P_NC-Pad45)") (class "Default")
      (node (ref "U8") (pin "45") (pinfunction "XTAL_P_NC_45") (pintype "passive"))
    )
    (net (code "110") (name "unconnected-(st1-NC-Pad9)") (class "Default")
      (node (ref "st1") (pin "9") (pinfunction "NC_9") (pintype "passive"))
    )
    (net (code "111") (name "unconnected-(st1-TP0-Pad1)") (class "Default")
      (node (ref "st1") (pin "1") (pinfunction "TP0_1") (pintype "passive"))
    )
    (net (code "112") (name "unconnected-(st1-TP1-Pad2)") (class "Default")
      (node (ref "st1") (pin "2") (pinfunction "TP1_2") (pintype "passive"))
    )
  )
)
